# GPS.net
KiCad netlist of a schematic drawn in Altium Designer
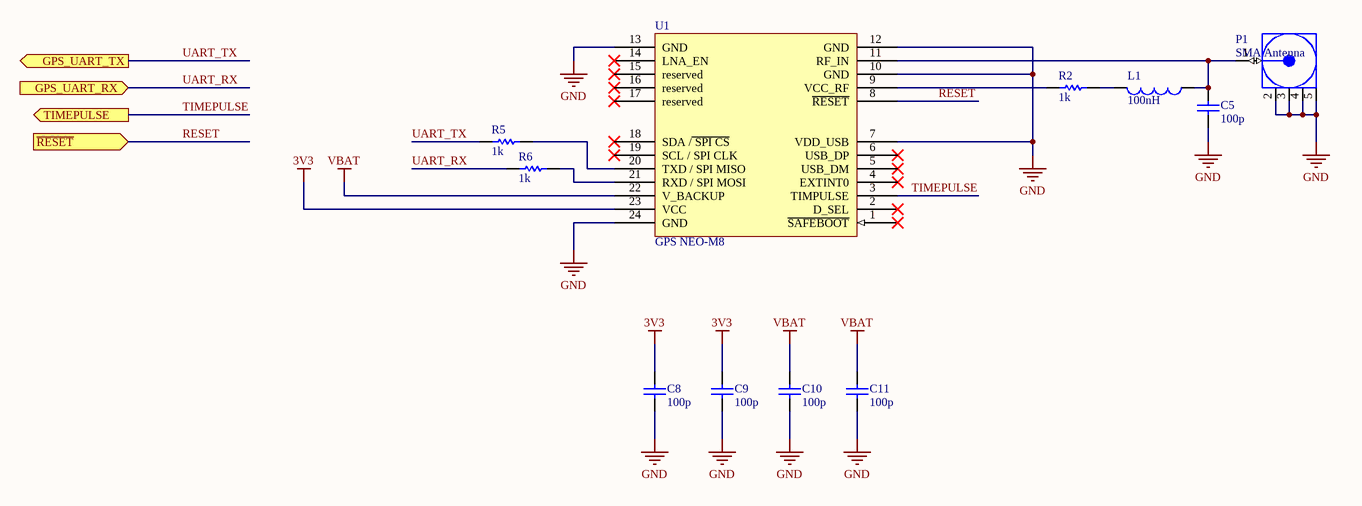
[diagram p0: GPS.SchDoc]

(export (version "E")
  (design (tool "Eeschema 10.0.6"))
  (components
    (comp (ref "C5")
      (value "100p")
      (footprint "agh_racing_2018:CAP_0603_IPC_MD")
      (description "Capacitor")
      (fields (field (name "Comment") "Cap"))
      (libsource (lib "agh_racing_2018") (part "Cap"))
    )
    (comp (ref "C8")
      (value "100p")
      (footprint "agh_racing_2018:CAP_0603_IPC_MD")
      (description "Capacitor")
      (fields (field (name "Comment") "Cap"))
      (libsource (lib "agh_racing_2018") (part "Cap"))
    )
    (comp (ref "C9")
      (value "100p")
      (footprint "agh_racing_2018:CAP_0603_IPC_MD")
      (description "Capacitor")
      (fields (field (name "Comment") "Cap"))
      (libsource (lib "agh_racing_2018") (part "Cap"))
    )
    (comp (ref "C10")
      (value "100p")
      (footprint "agh_racing_2018:CAP_0603_IPC_MD")
      (description "Capacitor")
      (fields (field (name "Comment") "Cap"))
      (libsource (lib "agh_racing_2018") (part "Cap"))
    )
    (comp (ref "C11")
      (value "100p")
      (footprint "agh_racing_2018:CAP_0603_IPC_MD")
      (description "Capacitor")
      (fields (field (name "Comment") "Cap"))
      (libsource (lib "agh_racing_2018") (part "Cap"))
    )
    (comp (ref "L1")
      (value "100nH")
      (footprint "agh_racing_2018:IND_0603_IPC_HD")
      (description "Inductor")
      (fields (field (name "Comment") "Ind"))
      (libsource (lib "agh_racing_2018") (part "Ind"))
    )
    (comp (ref "P1")
      (value "SMA Antenna")
      (footprint "SMA_PCB_Female_Angle_connector")
      (description "Gniazdo; SMA; żeńskie; kątowe 90°; 50Ω; THT; na PCB; teflon; złocony")
      (libsource (lib "agh_racing_2018") (part "SMA PCB Female Antenna Angle connector"))
    )
    (comp (ref "R2")
      (value "1k")
      (footprint "agh_racing_2018:RES_0603_IPC_MD")
      (description "Resistor")
      (fields (field (name "Comment") "Res"))
      (libsource (lib "agh_racing_2018") (part "Res"))
    )
    (comp (ref "R5")
      (value "1k")
      (footprint "agh_racing_2018:RES_0603_IPC_MD")
      (description "Resistor")
      (fields (field (name "Comment") "Res"))
      (libsource (lib "agh_racing_2018") (part "Res"))
    )
    (comp (ref "R6")
      (value "1k")
      (footprint "agh_racing_2018:RES_0603_IPC_MD")
      (description "Resistor")
      (fields (field (name "Comment") "Res"))
      (libsource (lib "agh_racing_2018") (part "Res"))
    )
    (comp (ref "U1")
      (value "GPS NEO-M8")
      (footprint "NEO")
      (libsource (lib "agh_racing_2018") (part "u-blox NEO-M8"))
    )
  )
  (nets
    (net (code "1") (name "/RESET") (class "Default")
      (node (ref "U1") (pin "8") (pinfunction "~{RESET}_8") (pintype "passive"))
    )
    (net (code "2") (name "/TIMEPULSE") (class "Default")
      (node (ref "U1") (pin "3") (pinfunction "TIMPULSE_3") (pintype "passive"))
    )
    (net (code "3") (name "/UART_RX") (class "Default")
      (node (ref "R6") (pin "1") (pinfunction "1_1") (pintype "passive"))
    )
    (net (code "4") (name "/UART_TX") (class "Default")
      (node (ref "R5") (pin "1") (pinfunction "1_1") (pintype "passive"))
    )
    (net (code "5") (name "3V3") (class "Default")
      (node (ref "C8") (pin "2") (pinfunction "2_2") (pintype "passive"))
      (node (ref "C9") (pin "2") (pinfunction "2_2") (pintype "passive"))
      (node (ref "U1") (pin "23") (pinfunction "VCC_23") (pintype "passive"))
    )
    (net (code "6") (name "GND") (class "Default")
      (node (ref "C10") (pin "1") (pinfunction "1_1") (pintype "passive"))
      (node (ref "C11") (pin "1") (pinfunction "1_1") (pintype "passive"))
      (node (ref "C5") (pin "1") (pinfunction "1_1") (pintype "passive"))
      (node (ref "C8") (pin "1") (pinfunction "1_1") (pintype "passive"))
      (node (ref "C9") (pin "1") (pinfunction "1_1") (pintype "passive"))
      (node (ref "P1") (pin "2") (pinfunction "GND_2") (pintype "power_in"))
      (node (ref "P1") (pin "3") (pinfunction "GND_3") (pintype "power_in"))
      (node (ref "P1") (pin "4") (pinfunction "GND_4") (pintype "power_in"))
      (node (ref "P1") (pin "5") (pinfunction "GND_5") (pintype "power_in"))
      (node (ref "U1") (pin "10") (pinfunction "GND_10") (pintype "passive"))
      (node (ref "U1") (pin "12") (pinfunction "GND_12") (pintype "passive"))
      (node (ref "U1") (pin "13") (pinfunction "GND_13") (pintype "passive"))
      (node (ref "U1") (pin "24") (pinfunction "GND_24") (pintype "passive"))
      (node (ref "U1") (pin "7") (pinfunction "VDD_USB_7") (pintype "passive"))
    )
    (net (code "7") (name "Net-(L1-Pad2)") (class "Default")
      (node (ref "L1") (pin "2") (pinfunction "2_2") (pintype "passive"))
      (node (ref "R2") (pin "1") (pinfunction "1_1") (pintype "passive"))
    )
    (net (code "8") (name "Net-(P1-Signal)") (class "Default")
      (node (ref "C5") (pin "2") (pinfunction "2_2") (pintype "passive"))
      (node (ref "L1") (pin "1") (pinfunction "1_1") (pintype "passive"))
      (node (ref "P1") (pin "1") (pinfunction "Signal_1") (pintype "bidirectional"))
      (node (ref "U1") (pin "11") (pinfunction "RF_IN_11") (pintype "passive"))
    )
    (net (code "9") (name "Net-(U1-RXD_{slash}_SPI_MOSI)") (class "Default")
      (node (ref "R6") (pin "2") (pinfunction "2_2") (pintype "passive"))
      (node (ref "U1") (pin "21") (pinfunction "RXD_/_SPI_MOSI_21") (pintype "passive"))
    )
    (net (code "10") (name "Net-(U1-TXD_{slash}_SPI_MISO)") (class "Default")
      (node (ref "R5") (pin "2") (pinfunction "2_2") (pintype "passive"))
      (node (ref "U1") (pin "20") (pinfunction "TXD_/_SPI_MISO_20") (pintype "passive"))
    )
    (net (code "11") (name "Net-(U1-VCC_RF)") (class "Default")
      (node (ref "R2") (pin "2") (pinfunction "2_2") (pintype "passive"))
      (node (ref "U1") (pin "9") (pinfunction "VCC_RF_9") (pintype "passive"))
    )
    (net (code "12") (name "VBAT") (class "Default")
      (node (ref "C10") (pin "2") (pinfunction "2_2") (pintype "passive"))
      (node (ref "C11") (pin "2") (pinfunction "2_2") (pintype "passive"))
      (node (ref "U1") (pin "22") (pinfunction "V_BACKUP_22") (pintype "passive"))
    )
    (net (code "13") (name "unconnected-(U1-D_SEL-Pad2)") (class "Default")
      (node (ref "U1") (pin "2") (pinfunction "D_SEL_2") (pintype "passive+no_connect"))
    )
    (net (code "14") (name "unconnected-(U1-EXTINT0-Pad4)") (class "Default")
      (node (ref "U1") (pin "4") (pinfunction "EXTINT0_4") (pintype "passive+no_connect"))
    )
    (net (code "15") (name "unconnected-(U1-LNA_EN-Pad14)") (class "Default")
      (node (ref "U1") (pin "14") (pinfunction "LNA_EN_14") (pintype "passive+no_connect"))
    )
    (net (code "16") (name "unconnected-(U1-SCL_{slash}_SPI_CLK-Pad19)") (class "Default")
      (node (ref "U1") (pin "19") (pinfunction "SCL_/_SPI_CLK_19") (pintype "passive+no_connect"))
    )
    (net (code "17") (name "unconnected-(U1-SDA_{slash}~{_SPI_CS}-Pad18)") (class "Default")
      (node (ref "U1") (pin "18") (pinfunction "SDA_/~{_SPI_CS}_18") (pintype "passive+no_connect"))
    )
    (net (code "18") (name "unconnected-(U1-USB_DM-Pad5)") (class "Default")
      (node (ref "U1") (pin "5") (pinfunction "USB_DM_5") (pintype "passive+no_connect"))
    )
    (net (code "19") (name "unconnected-(U1-USB_DP-Pad6)") (class "Default")
      (node (ref "U1") (pin "6") (pinfunction "USB_DP_6") (pintype "passive+no_connect"))
    )
    (net (code "20") (name "unconnected-(U1-reserved-Pad15)") (class "Default")
      (node (ref "U1") (pin "15") (pinfunction "reserved_15") (pintype "passive+no_connect"))
    )
    (net (code "21") (name "unconnected-(U1-reserved-Pad16)") (class "Default")
      (node (ref "U1") (pin "16") (pinfunction "reserved_16") (pintype "passive+no_connect"))
    )
    (net (code "22") (name "unconnected-(U1-reserved-Pad17)") (class "Default")
      (node (ref "U1") (pin "17") (pinfunction "reserved_17") (pintype "passive+no_connect"))
    )
    (net (code "23") (name "unconnected-(U1-~{SAFEBOOT}-Pad1)") (class "Default")
      (node (ref "U1") (pin "1") (pinfunction "~{SAFEBOOT}_1") (pintype "input+no_connect"))
    )
  )
)
